# SFPplusConn.net
KiCad netlist of a schematic drawn in Altium Designer
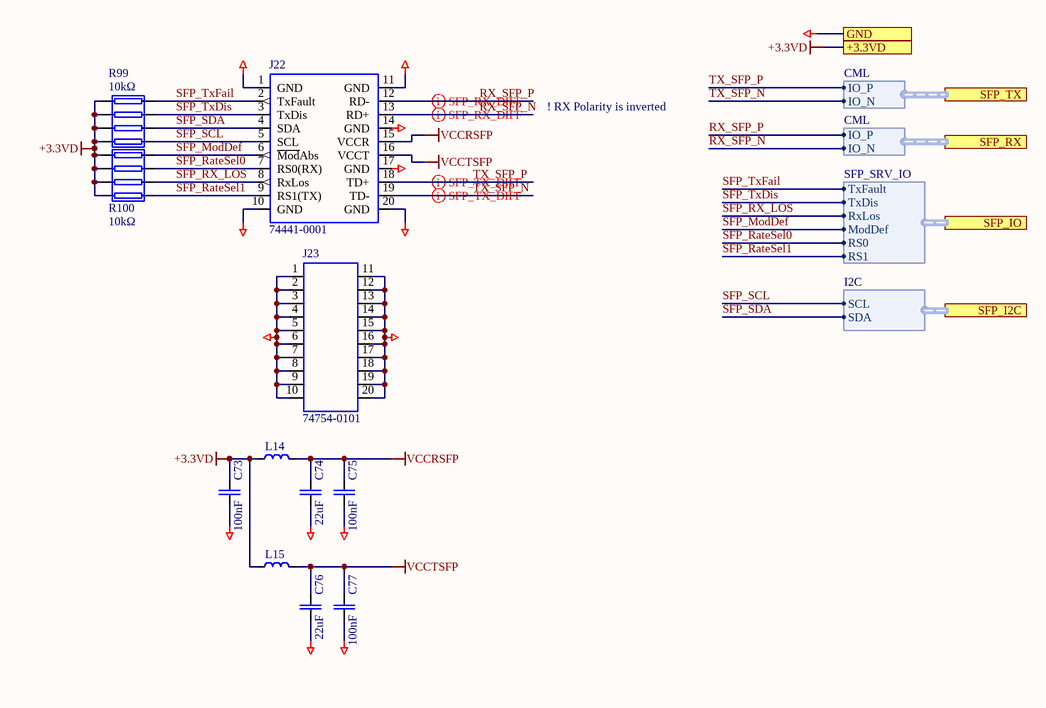
[diagram p0: SFPplusConn.SchDoc]

(export (version "E")
  (design (tool "Eeschema 10.0.6"))
  (components
    (comp (ref "C73")
      (value "100nF")
      (footprint "CAPC1608N")
      (description "Generic ceramic SMD capacitor")
      (fields (field (name "MAINTAINER") "Evgeniy Kotov"))
      (libsource (lib "[Capacitors] Capacitors SMD") (part "CAPC"))
    )
    (comp (ref "C74")
      (value "22uF")
      (footprint "CAPC2012N")
      (description "Generic ceramic SMD capacitor")
      (fields (field (name "MAINTAINER") "Evgeniy Kotov"))
      (libsource (lib "[Capacitors] Capacitors SMD") (part "CAPC"))
    )
    (comp (ref "C75")
      (value "100nF")
      (footprint "CAPC1608N")
      (description "Generic ceramic SMD capacitor")
      (fields (field (name "MAINTAINER") "Evgeniy Kotov"))
      (libsource (lib "[Capacitors] Capacitors SMD") (part "CAPC"))
    )
    (comp (ref "C76")
      (value "22uF")
      (footprint "CAPC2012N")
      (description "Generic ceramic SMD capacitor")
      (fields (field (name "MAINTAINER") "Evgeniy Kotov"))
      (libsource (lib "[Capacitors] Capacitors SMD") (part "CAPC"))
    )
    (comp (ref "C77")
      (value "100nF")
      (footprint "CAPC1608N")
      (description "Generic ceramic SMD capacitor")
      (fields (field (name "MAINTAINER") "Evgeniy Kotov"))
      (libsource (lib "[Capacitors] Capacitors SMD") (part "CAPC"))
    )
    (comp (ref "J22")
      (value "74441-0001")
      (footprint "MOLEX_74441-0001")
      (description "CONN SFP+ RCPT 20POS SLD R/A SMD")
      (libsource (lib "[Connectors] Miscellaneous") (part "MOLEX-74441-0001"))
    )
    (comp (ref "J23")
      (value "74754-0101")
      (footprint "MOLEX_74737-0111")
      (description "SFP+ Cage, Single Port, Height 10.85 mm, Tail Height 3.05 mm, -40 to 85 degC, RoHS, Tray")
      (libsource (lib "[Connectors] Miscellaneous") (part "MOLX-74754-0101"))
    )
    (comp (ref "L14")
      (value "BLM21PG221SN1")
      (footprint "INDC2012N")
      (description "Ferrite Beads, 0805, 220 Ohm, 2A")
      (fields (field (name "TOLERANCE") "25%") (field (name "MAINTAINER") "Evgeniy Kotov"))
      (libsource (lib "[Inductors & Transformers] Inductors SMD") (part "BLM21PG221SN1"))
    )
    (comp (ref "L15")
      (value "BLM21PG221SN1")
      (footprint "INDC2012N")
      (description "Ferrite Beads, 0805, 220 Ohm, 2A")
      (fields (field (name "TOLERANCE") "25%") (field (name "MAINTAINER") "Evgeniy Kotov"))
      (libsource (lib "[Inductors & Transformers] Inductors SMD") (part "BLM21PG221SN1"))
    )
    (comp (ref "R99")
      (value "10kΩ")
      (footprint "CAY16-J4")
      (fields (field (name "Comment") "CAY16-1002F4LF") (field (name "MAINTAINER") "Anton Pavlenko"))
      (libsource (lib "[Resistors] Resistors SMD") (part "RESPACK4"))
    )
    (comp (ref "R100")
      (value "10kΩ")
      (footprint "CAY16-J4")
      (fields (field (name "Comment") "CAY16-1002F4LF") (field (name "MAINTAINER") "Anton Pavlenko"))
      (libsource (lib "[Resistors] Resistors SMD") (part "RESPACK4"))
    )
  )
  (nets
    (net (code "4") (name "+3.3VD") (class "Default")
      (node (ref "C73") (pin "2") (pintype "passive"))
      (node (ref "L14") (pin "1") (pinfunction "1_1") (pintype "passive"))
      (node (ref "L15") (pin "1") (pinfunction "1_1") (pintype "passive"))
      (node (ref "R100") (pin "1") (pinfunction "1_1") (pintype "passive"))
      (node (ref "R100") (pin "2") (pinfunction "2_2") (pintype "passive"))
      (node (ref "R100") (pin "3") (pinfunction "3_3") (pintype "passive"))
      (node (ref "R100") (pin "4") (pinfunction "4_4") (pintype "passive"))
      (node (ref "R99") (pin "1") (pinfunction "1_1") (pintype "passive"))
      (node (ref "R99") (pin "2") (pinfunction "2_2") (pintype "passive"))
      (node (ref "R99") (pin "3") (pinfunction "3_3") (pintype "passive"))
      (node (ref "R99") (pin "4") (pinfunction "4_4") (pintype "passive"))
    )
    (net (code "5") (name "/RX_SFP_N") (class "Default")
      (node (ref "J22") (pin "13") (pinfunction "RD+_13") (pintype "passive"))
    )
    (net (code "6") (name "/RX_SFP_P") (class "Default")
      (node (ref "J22") (pin "12") (pinfunction "RD-_12") (pintype "passive"))
    )
    (net (code "7") (name "/SFP_ModDef") (class "Default")
      (node (ref "J22") (pin "6") (pinfunction "~{Mod}Abs_6") (pintype "output"))
      (node (ref "R100") (pin "8") (pinfunction "8_8") (pintype "passive"))
    )
    (net (code "8") (name "/SFP_RX_LOS") (class "Default")
      (node (ref "J22") (pin "8") (pinfunction "RxLos_8") (pintype "output"))
      (node (ref "R100") (pin "6") (pinfunction "6_6") (pintype "passive"))
    )
    (net (code "9") (name "/SFP_RateSel0") (class "Default")
      (node (ref "J22") (pin "7") (pinfunction "RS0(RX)_7") (pintype "passive"))
      (node (ref "R100") (pin "7") (pinfunction "7_7") (pintype "passive"))
    )
    (net (code "10") (name "/SFP_RateSel1") (class "Default")
      (node (ref "J22") (pin "9") (pinfunction "RS1(TX)_9") (pintype "passive"))
      (node (ref "R100") (pin "5") (pinfunction "5_5") (pintype "passive"))
    )
    (net (code "11") (name "/SFP_SCL") (class "Default")
      (node (ref "J22") (pin "5") (pinfunction "SCL_5") (pintype "passive"))
      (node (ref "R99") (pin "5") (pinfunction "5_5") (pintype "passive"))
    )
    (net (code "12") (name "/SFP_SDA") (class "Default")
      (node (ref "J22") (pin "4") (pinfunction "SDA_4") (pintype "passive"))
      (node (ref "R99") (pin "6") (pinfunction "6_6") (pintype "passive"))
    )
    (net (code "13") (name "/SFP_TxDis") (class "Default")
      (node (ref "J22") (pin "3") (pinfunction "TxDis_3") (pintype "passive"))
      (node (ref "R99") (pin "7") (pinfunction "7_7") (pintype "passive"))
    )
    (net (code "14") (name "/SFP_TxFail") (class "Default")
      (node (ref "J22") (pin "2") (pinfunction "TxFault_2") (pintype "output"))
      (node (ref "R99") (pin "8") (pinfunction "8_8") (pintype "passive"))
    )
    (net (code "15") (name "/TX_SFP_N") (class "Default")
      (node (ref "J22") (pin "19") (pinfunction "TD-_19") (pintype "passive"))
    )
    (net (code "16") (name "/TX_SFP_P") (class "Default")
      (node (ref "J22") (pin "18") (pinfunction "TD+_18") (pintype "passive"))
    )
    (net (code "20") (name "GND") (class "Default")
      (node (ref "C73") (pin "1") (pintype "passive"))
      (node (ref "C74") (pin "1") (pintype "passive"))
      (node (ref "C75") (pin "1") (pintype "passive"))
      (node (ref "C76") (pin "1") (pintype "passive"))
      (node (ref "C77") (pin "1") (pintype "passive"))
      (node (ref "J22") (pin "1") (pinfunction "GND_1") (pintype "passive"))
      (node (ref "J22") (pin "10") (pinfunction "GND_10") (pintype "passive"))
      (node (ref "J22") (pin "11") (pinfunction "GND_11") (pintype "passive"))
      (node (ref "J22") (pin "14") (pinfunction "GND_14") (pintype "passive"))
      (node (ref "J22") (pin "17") (pinfunction "GND_17") (pintype "passive"))
      (node (ref "J22") (pin "20") (pinfunction "GND_20") (pintype "passive"))
      (node (ref "J23") (pin "1") (pinfunction "1_1") (pintype "passive"))
      (node (ref "J23") (pin "10") (pinfunction "10_10") (pintype "passive"))
      (node (ref "J23") (pin "11") (pinfunction "11_11") (pintype "passive"))
      (node (ref "J23") (pin "12") (pinfunction "12_12") (pintype "passive"))
      (node (ref "J23") (pin "13") (pinfunction "13_13") (pintype "passive"))
      (node (ref "J23") (pin "14") (pinfunction "14_14") (pintype "passive"))
      (node (ref "J23") (pin "15") (pinfunction "15_15") (pintype "passive"))
      (node (ref "J23") (pin "16") (pinfunction "16_16") (pintype "passive"))
      (node (ref "J23") (pin "17") (pinfunction "17_17") (pintype "passive"))
      (node (ref "J23") (pin "18") (pinfunction "18_18") (pintype "passive"))
      (node (ref "J23") (pin "19") (pinfunction "19_19") (pintype "passive"))
      (node (ref "J23") (pin "2") (pinfunction "2_2") (pintype "passive"))
      (node (ref "J23") (pin "20") (pinfunction "20_20") (pintype "passive"))
      (node (ref "J23") (pin "3") (pinfunction "3_3") (pintype "passive"))
      (node (ref "J23") (pin "4") (pinfunction "4_4") (pintype "passive"))
      (node (ref "J23") (pin "5") (pinfunction "5_5") (pintype "passive"))
      (node (ref "J23") (pin "6") (pinfunction "6_6") (pintype "passive"))
      (node (ref "J23") (pin "7") (pinfunction "7_7") (pintype "passive"))
      (node (ref "J23") (pin "8") (pinfunction "8_8") (pintype "passive"))
      (node (ref "J23") (pin "9") (pinfunction "9_9") (pintype "passive"))
    )
    (net (code "21") (name "VCCRSFP") (class "Default")
      (node (ref "C74") (pin "2") (pintype "passive"))
      (node (ref "C75") (pin "2") (pintype "passive"))
      (node (ref "J22") (pin "15") (pinfunction "VCCR_15") (pintype "passive"))
      (node (ref "L14") (pin "2") (pinfunction "2_2") (pintype "passive"))
    )
    (net (code "22") (name "VCCTSFP") (class "Default")
      (node (ref "C76") (pin "2") (pintype "passive"))
      (node (ref "C77") (pin "2") (pintype "passive"))
      (node (ref "J22") (pin "16") (pinfunction "VCCT_16") (pintype "passive"))
      (node (ref "L15") (pin "2") (pinfunction "2_2") (pintype "passive"))
    )
  )
)
